# LD3985M33R.net
KiCad netlist of a schematic drawn in Altium Designer
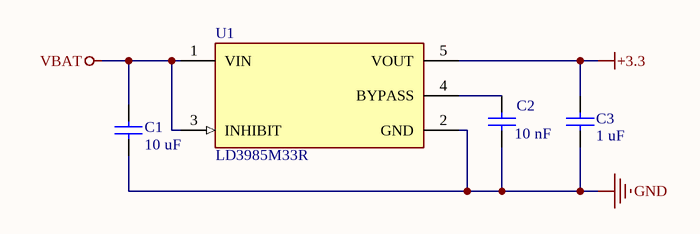
[diagram p0: LD3985M33R.SchDoc]

(export (version "E")
  (design (tool "Eeschema 10.0.6"))
  (components
    (comp (ref "C1")
      (value "10 uF")
      (footprint "CAPC1005X55X25NL05T10")
      (fields (field (name "MANUFACTURER") "Murata") (field (name "PART NUMBER") "GRM155F50J684ZE01D"))
      (libsource (lib "Altium Content Vault") (part "CAP"))
    )
    (comp (ref "C2")
      (value "10 nF")
      (footprint "CAPC1005X55X25NL05T10")
      (fields (field (name "MANUFACTURER") "Murata") (field (name "PART NUMBER") "GRM155F50J684ZE01D"))
      (libsource (lib "Altium Content Vault") (part "CAP"))
    )
    (comp (ref "C3")
      (value "1 uF")
      (footprint "CAPC1005X55X25NL05T10")
      (fields (field (name "MANUFACTURER") "Murata") (field (name "PART NUMBER") "GRM155F50J684ZE01D"))
      (libsource (lib "Altium Content Vault") (part "CAP"))
    )
    (comp (ref "U1")
      (value "LD3985M33R")
      (footprint "FP-SOT23-5L-7049676-MFG")
      (description "IC REG LINEAR 3.3V 150MA SOT23-5")
      (libsource (lib "Altium Content Vault") (part "aba04f4e281572ab958dbcc456c8333"))
    )
  )
  (nets
    (net (code "1") (name "+3.3") (class "Default")
      (node (ref "C3") (pin "2") (pinfunction "2_2") (pintype "passive"))
      (node (ref "U1") (pin "5") (pinfunction "VOUT_5") (pintype "passive"))
    )
    (net (code "2") (name "GND") (class "Default")
      (node (ref "C1") (pin "1") (pinfunction "1_1") (pintype "passive"))
      (node (ref "C2") (pin "1") (pinfunction "1_1") (pintype "passive"))
      (node (ref "C3") (pin "1") (pinfunction "1_1") (pintype "passive"))
      (node (ref "U1") (pin "2") (pinfunction "GND_2") (pintype "power_in"))
    )
    (net (code "3") (name "Net-(U1-BYPASS)") (class "Default")
      (node (ref "C2") (pin "2") (pinfunction "2_2") (pintype "passive"))
      (node (ref "U1") (pin "4") (pinfunction "BYPASS_4") (pintype "passive"))
    )
    (net (code "4") (name "VBAT") (class "Default")
      (node (ref "C1") (pin "2") (pinfunction "2_2") (pintype "passive"))
      (node (ref "U1") (pin "1") (pinfunction "VIN_1") (pintype "power_in"))
      (node (ref "U1") (pin "3") (pinfunction "INHIBIT_3") (pintype "input"))
    )
  )
)
